# LM94022TmpBoard.net
KiCad netlist of a schematic drawn in EAGLE
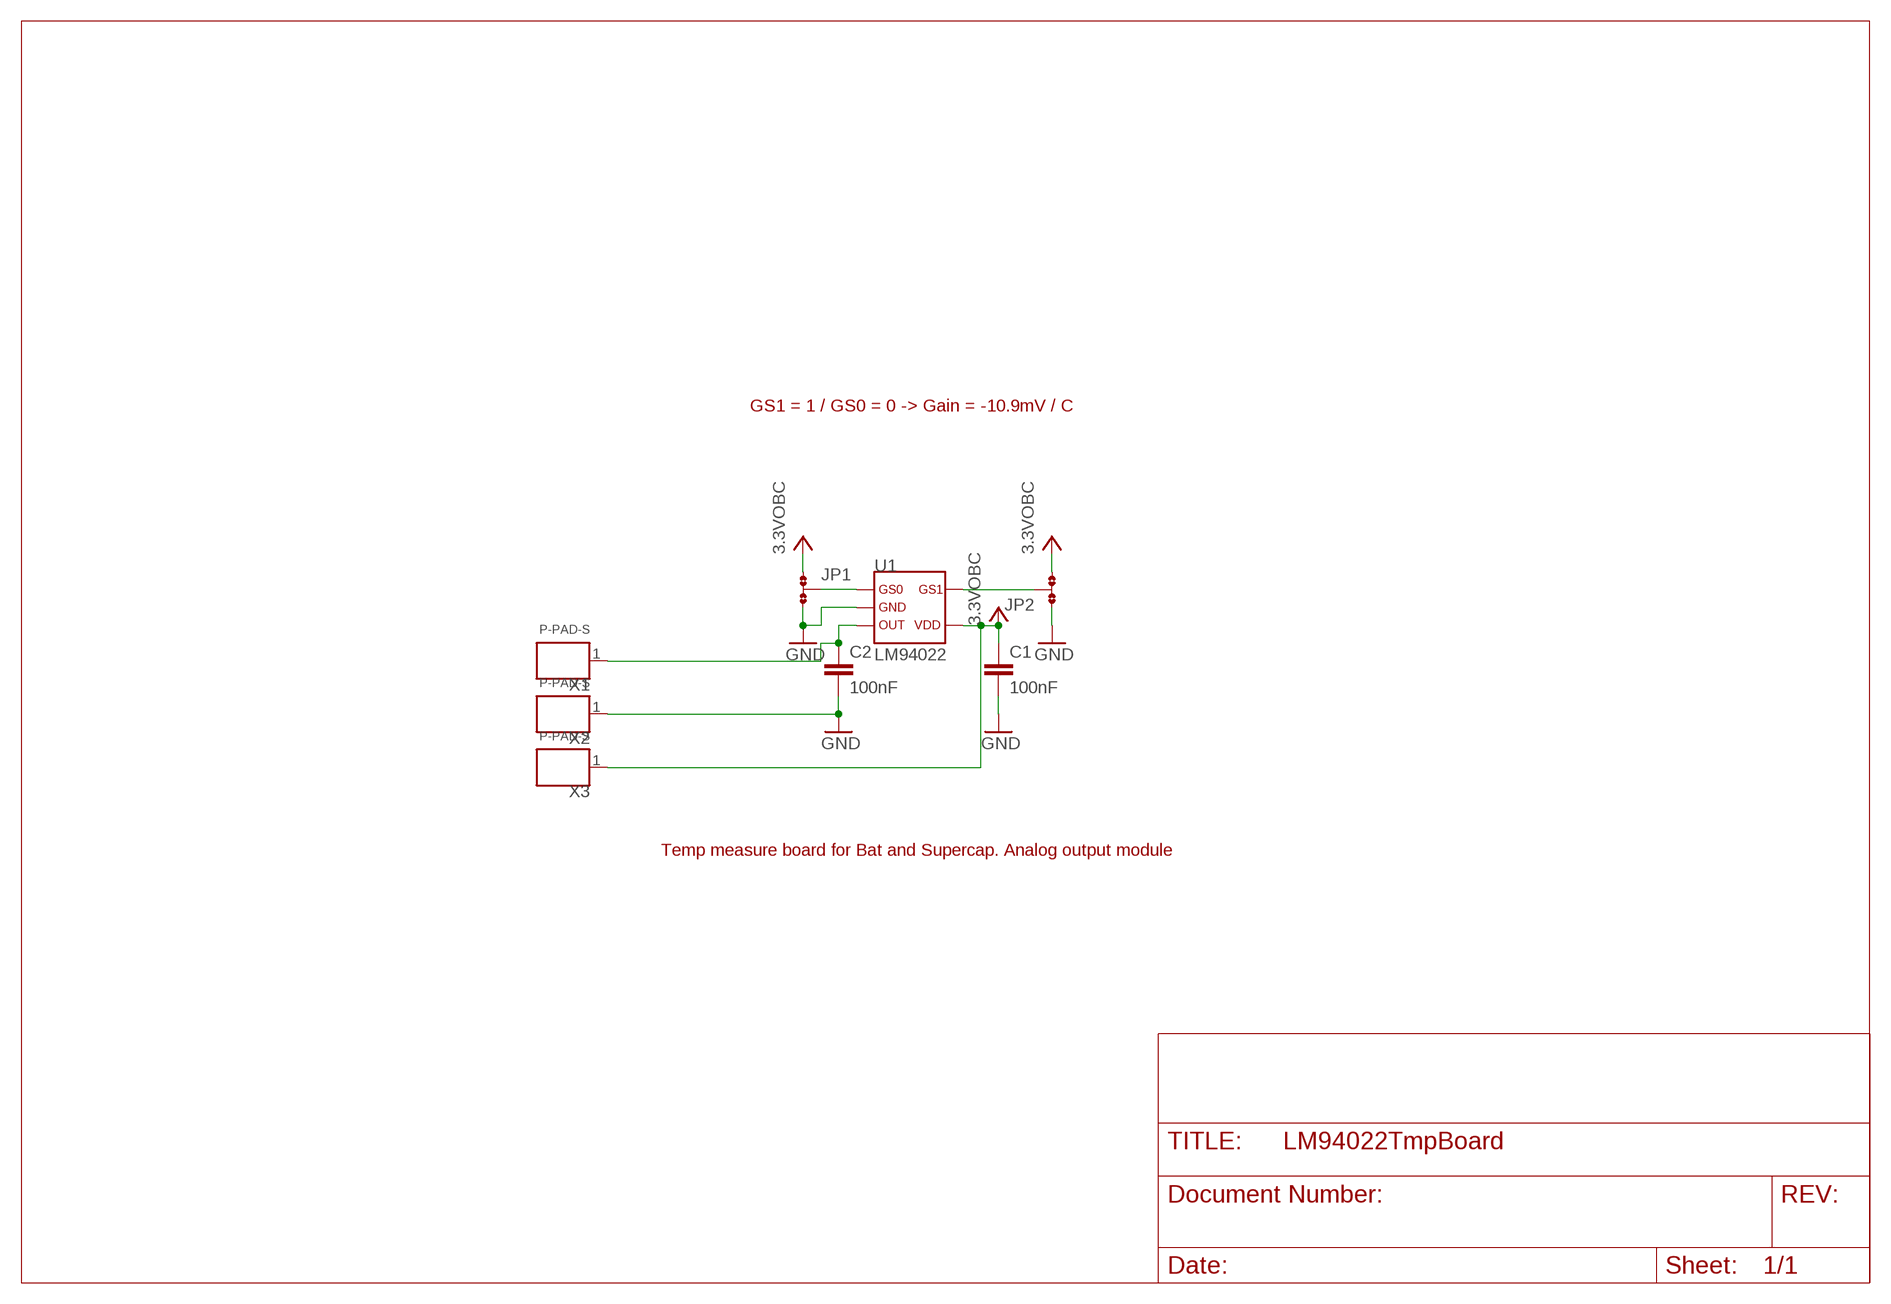
[diagram p0: schematic, sheet 1]

(export (version "E")
  (design (tool "Eeschema 10.0.6"))
  (components
    (comp (ref "C1")
      (value "100nF")
      (footprint "eagle-import:C0603(1608)")
      (libsource (lib "eagle-import") (part "C0603(1608)"))
    )
    (comp (ref "C2")
      (value "100nF")
      (footprint "eagle-import:C0603(1608)")
      (libsource (lib "eagle-import") (part "C0603(1608)"))
    )
    (comp (ref "JP1")
      (value "JP2")
      (footprint "eagle-import:JP2SMD0603")
      (libsource (lib "eagle-import") (part "JP2"))
    )
    (comp (ref "JP2")
      (value "JP2")
      (footprint "eagle-import:JP2SMD0603")
      (libsource (lib "eagle-import") (part "JP2"))
    )
    (comp (ref "U1")
      (value "LM94022")
      (footprint "eagle-import:SC70-5")
      (libsource (lib "eagle-import") (part "LM94022"))
    )
    (comp (ref "X1")
      (value "P-PAD-S")
      (footprint "eagle-import:P-PAD-S")
      (libsource (lib "eagle-import") (part "P-PAD-S"))
    )
    (comp (ref "X2")
      (value "P-PAD-S")
      (footprint "eagle-import:P-PAD-S")
      (libsource (lib "eagle-import") (part "P-PAD-S"))
    )
    (comp (ref "X3")
      (value "P-PAD-S")
      (footprint "eagle-import:P-PAD-S")
      (libsource (lib "eagle-import") (part "P-PAD-S"))
    )
  )
  (nets
    (net (code "1") (name "3.3VOBC") (class "Default")
      (node (ref "C1") (pin "1") (pinfunction "1_1") (pintype "passive"))
      (node (ref "JP1") (pin "1") (pinfunction "1_1") (pintype "passive"))
      (node (ref "JP2") (pin "3") (pinfunction "3_3") (pintype "passive"))
      (node (ref "U1") (pin "P$4") (pinfunction "P$4_P$4") (pintype "power_in"))
      (node (ref "X3") (pin "1") (pinfunction "P$1_1") (pintype "bidirectional"))
    )
    (net (code "2") (name "GND") (class "Default")
      (node (ref "C1") (pin "2") (pinfunction "2_2") (pintype "passive"))
      (node (ref "C2") (pin "2") (pinfunction "2_2") (pintype "passive"))
      (node (ref "JP1") (pin "3") (pinfunction "3_3") (pintype "passive"))
      (node (ref "JP2") (pin "1") (pinfunction "1_1") (pintype "passive"))
      (node (ref "U1") (pin "P$2") (pinfunction "P$2_P$2") (pintype "power_in"))
      (node (ref "X2") (pin "1") (pinfunction "P$1_1") (pintype "bidirectional"))
    )
    (net (code "3") (name "Net-(JP1-Pad2)") (class "Default")
      (node (ref "JP1") (pin "2") (pinfunction "2_2") (pintype "passive"))
      (node (ref "U1") (pin "P$1") (pinfunction "P$1_P$1") (pintype "passive"))
    )
    (net (code "4") (name "Net-(JP2-Pad2)") (class "Default")
      (node (ref "JP2") (pin "2") (pinfunction "2_2") (pintype "passive"))
      (node (ref "U1") (pin "P$5") (pinfunction "P$5_P$5") (pintype "passive"))
    )
    (net (code "5") (name "Net-(X1-P$1)") (class "Default")
      (node (ref "C2") (pin "1") (pinfunction "1_1") (pintype "passive"))
      (node (ref "U1") (pin "P$3") (pinfunction "P$3_P$3") (pintype "output"))
      (node (ref "X1") (pin "1") (pinfunction "P$1_1") (pintype "bidirectional"))
    )
  )
)
